# Sheet1.net
KiCad netlist of a schematic drawn in Altium Designer
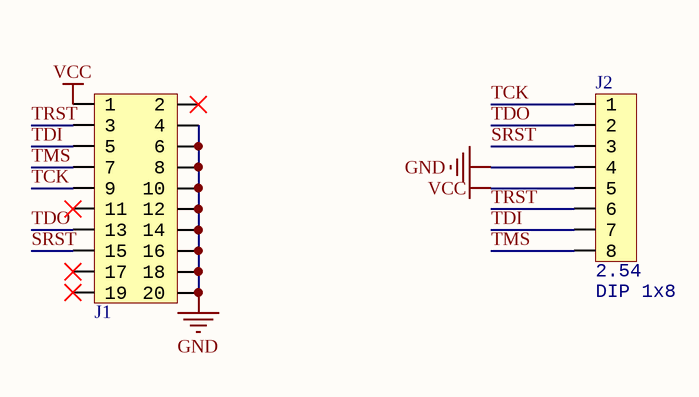
[diagram p0: Sheet1.SchDoc]

(export (version "E")
  (design (tool "Eeschema 10.0.6"))
  (components
    (comp (ref "J1")
      (value "HDR2x10")
      (footprint "JTAG-20P-2.54")
      (description "Header")
      (libsource (lib "Integrated_Library") (part "HDR2x10_2.54"))
    )
    (comp (ref "J2")
      (value "2.54")
      (footprint "HDR1X8_2.54_180F")
      (description "Header")
      (fields (field (name "TYPE") "DIP 1x8") (field (name "Comment") "HDR1x8"))
      (libsource (lib "Integrated_Library") (part "HDR1x8_2.54"))
    )
  )
  (nets
    (net (code "1") (name "/SRST") (class "Default")
      (node (ref "J1") (pin "15") (pinfunction "15_15") (pintype "passive"))
      (node (ref "J2") (pin "3") (pinfunction "3_3") (pintype "passive"))
    )
    (net (code "2") (name "/TCK") (class "Default")
      (node (ref "J1") (pin "9") (pinfunction "9_9") (pintype "passive"))
      (node (ref "J2") (pin "1") (pinfunction "1_1") (pintype "passive"))
    )
    (net (code "3") (name "/TDI") (class "Default")
      (node (ref "J1") (pin "5") (pinfunction "5_5") (pintype "passive"))
      (node (ref "J2") (pin "7") (pinfunction "7_7") (pintype "passive"))
    )
    (net (code "4") (name "/TDO") (class "Default")
      (node (ref "J1") (pin "13") (pinfunction "13_13") (pintype "passive"))
      (node (ref "J2") (pin "2") (pinfunction "2_2") (pintype "passive"))
    )
    (net (code "5") (name "/TMS") (class "Default")
      (node (ref "J1") (pin "7") (pinfunction "7_7") (pintype "passive"))
      (node (ref "J2") (pin "8") (pinfunction "8_8") (pintype "passive"))
    )
    (net (code "6") (name "/TRST") (class "Default")
      (node (ref "J1") (pin "3") (pinfunction "3_3") (pintype "passive"))
      (node (ref "J2") (pin "6") (pinfunction "6_6") (pintype "passive"))
    )
    (net (code "7") (name "GND") (class "Default")
      (node (ref "J1") (pin "10") (pinfunction "10_10") (pintype "passive"))
      (node (ref "J1") (pin "12") (pinfunction "12_12") (pintype "passive"))
      (node (ref "J1") (pin "14") (pinfunction "14_14") (pintype "passive"))
      (node (ref "J1") (pin "16") (pinfunction "16_16") (pintype "passive"))
      (node (ref "J1") (pin "18") (pinfunction "18_18") (pintype "passive"))
      (node (ref "J1") (pin "20") (pinfunction "20_20") (pintype "passive"))
      (node (ref "J1") (pin "4") (pinfunction "4_4") (pintype "passive"))
      (node (ref "J1") (pin "6") (pinfunction "6_6") (pintype "passive"))
      (node (ref "J1") (pin "8") (pinfunction "8_8") (pintype "passive"))
      (node (ref "J2") (pin "4") (pinfunction "4_4") (pintype "passive"))
    )
    (net (code "8") (name "VCC") (class "Default")
      (node (ref "J1") (pin "1") (pinfunction "1_1") (pintype "passive"))
      (node (ref "J2") (pin "5") (pinfunction "5_5") (pintype "passive"))
    )
    (net (code "9") (name "unconnected-(J1-Pad2)") (class "Default")
      (node (ref "J1") (pin "2") (pinfunction "2_2") (pintype "passive+no_connect"))
    )
    (net (code "10") (name "unconnected-(J1-Pad11)") (class "Default")
      (node (ref "J1") (pin "11") (pinfunction "11_11") (pintype "passive+no_connect"))
    )
    (net (code "11") (name "unconnected-(J1-Pad17)") (class "Default")
      (node (ref "J1") (pin "17") (pinfunction "17_17") (pintype "passive+no_connect"))
    )
    (net (code "12") (name "unconnected-(J1-Pad19)") (class "Default")
      (node (ref "J1") (pin "19") (pinfunction "19_19") (pintype "passive+no_connect"))
    )
  )
)
